# Shield00.net
KiCad netlist of a schematic drawn in EAGLE
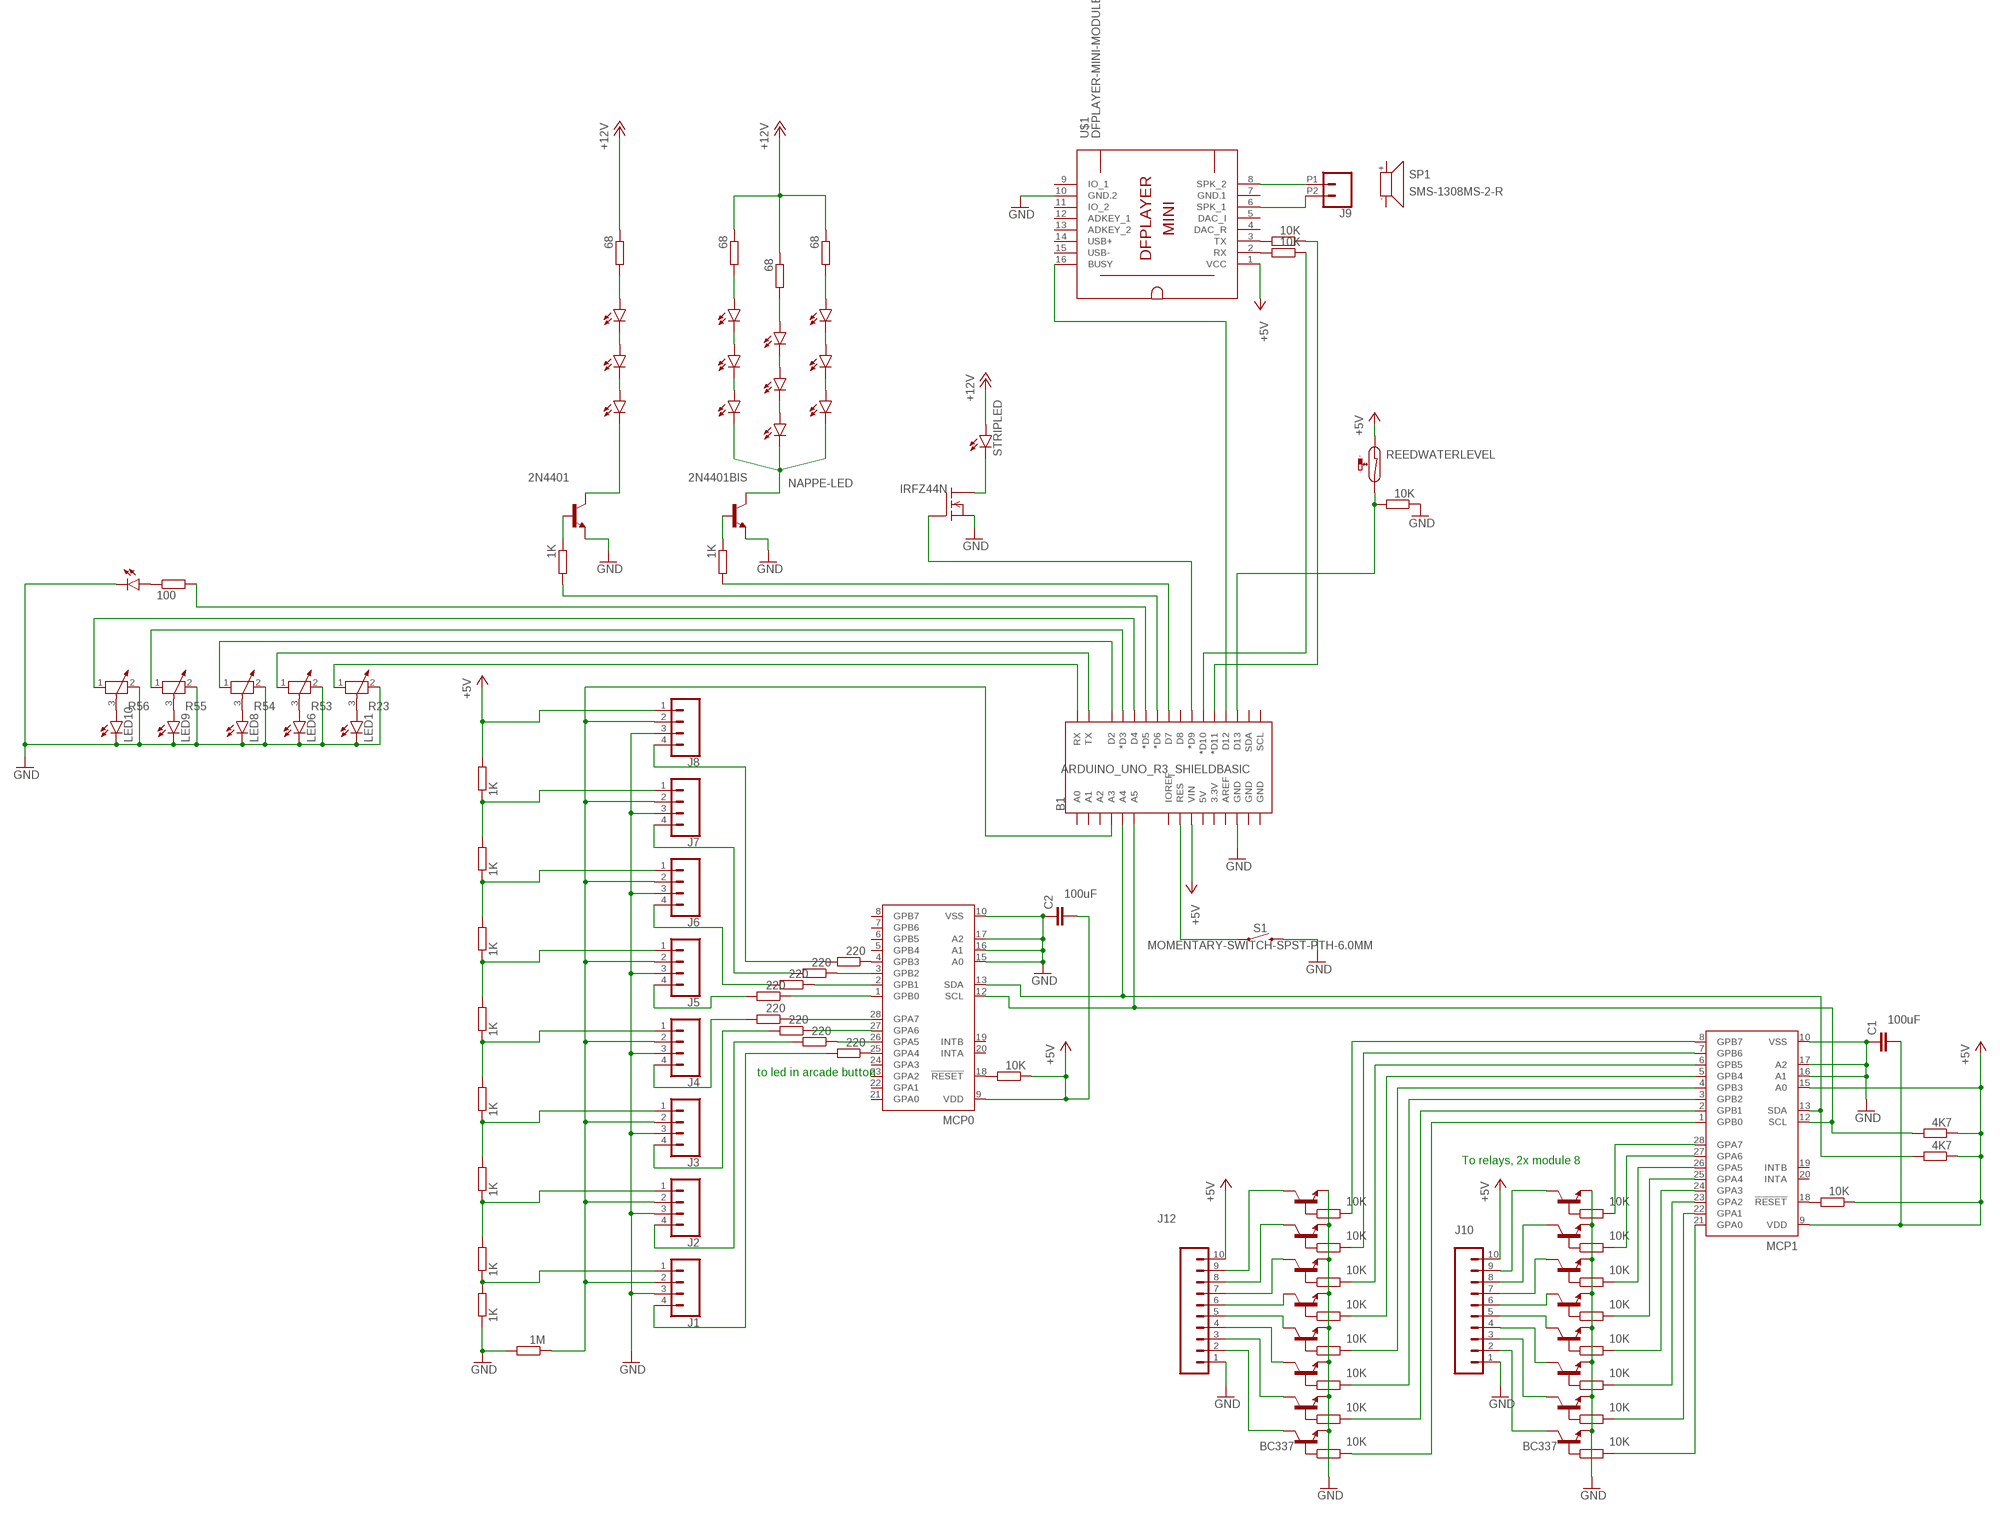
[diagram p0: schematic, sheet 1]

(export (version "E")
  (design (tool "Eeschema 10.0.6"))
  (components
    (comp (ref "2N4401")
      (value "2N4416")
      (footprint "eagle-import:TO92")
      (libsource (lib "eagle-import") (part "2N4416"))
    )
    (comp (ref "2N4401BIS")
      (value "2N4416")
      (footprint "eagle-import:TO92")
      (libsource (lib "eagle-import") (part "2N4416"))
    )
    (comp (ref "B1")
      (value "ARDUINO_UNO_R3_SHIELDBASIC")
      (footprint "eagle-import:UNO_R3_SHIELD")
      (libsource (lib "eagle-import") (part "ARDUINO_UNO_R3_SHIELDBASIC"))
    )
    (comp (ref "C1")
      (value "100uF")
      (footprint "eagle-import:C5B3")
      (libsource (lib "eagle-import") (part "C5/3"))
    )
    (comp (ref "C2")
      (value "100uF")
      (footprint "eagle-import:C5B3")
      (libsource (lib "eagle-import") (part "C5/3"))
    )
    (comp (ref "IRFZ44N")
      (value "IRF840")
      (footprint "eagle-import:TO220")
      (libsource (lib "eagle-import") (part "IRF840"))
    )
    (comp (ref "J1")
      (value "CONN_04JST-PTH-VERT")
      (footprint "eagle-import:JST-4-PTH-VERT")
      (libsource (lib "eagle-import") (part "CONN_04JST-PTH-VERT"))
    )
    (comp (ref "J2")
      (value "CONN_04JST-PTH-VERT")
      (footprint "eagle-import:JST-4-PTH-VERT")
      (libsource (lib "eagle-import") (part "CONN_04JST-PTH-VERT"))
    )
    (comp (ref "J3")
      (value "CONN_04JST-PTH-VERT")
      (footprint "eagle-import:JST-4-PTH-VERT")
      (libsource (lib "eagle-import") (part "CONN_04JST-PTH-VERT"))
    )
    (comp (ref "J4")
      (value "CONN_04JST-PTH-VERT")
      (footprint "eagle-import:JST-4-PTH-VERT")
      (libsource (lib "eagle-import") (part "CONN_04JST-PTH-VERT"))
    )
    (comp (ref "J5")
      (value "CONN_04JST-PTH-VERT")
      (footprint "eagle-import:JST-4-PTH-VERT")
      (libsource (lib "eagle-import") (part "CONN_04JST-PTH-VERT"))
    )
    (comp (ref "J6")
      (value "CONN_04JST-PTH-VERT")
      (footprint "eagle-import:JST-4-PTH-VERT")
      (libsource (lib "eagle-import") (part "CONN_04JST-PTH-VERT"))
    )
    (comp (ref "J7")
      (value "CONN_04JST-PTH-VERT")
      (footprint "eagle-import:JST-4-PTH-VERT")
      (libsource (lib "eagle-import") (part "CONN_04JST-PTH-VERT"))
    )
    (comp (ref "J8")
      (value "CONN_04JST-PTH-VERT")
      (footprint "eagle-import:JST-4-PTH-VERT")
      (libsource (lib "eagle-import") (part "CONN_04JST-PTH-VERT"))
    )
    (comp (ref "J9")
      (value "CONN_022.54MM_SCREWTERM")
      (footprint "eagle-import:1X02_2.54_SCREWTERM")
      (libsource (lib "eagle-import") (part "CONN_022.54MM_SCREWTERM"))
    )
    (comp (ref "J10")
      (value "CONN_10\"")
      (footprint "eagle-import:1X10")
      (libsource (lib "eagle-import") (part "CONN_10{dblquote}"))
    )
    (comp (ref "J12")
      (value "CONN_10\"")
      (footprint "eagle-import:1X10")
      (libsource (lib "eagle-import") (part "CONN_10{dblquote}"))
    )
    (comp (ref "LED1")
      (value "LED5MM")
      (footprint "eagle-import:LED5MM")
      (libsource (lib "eagle-import") (part "LED5MM"))
    )
    (comp (ref "LED6")
      (value "LED5MM")
      (footprint "eagle-import:LED5MM")
      (libsource (lib "eagle-import") (part "LED5MM"))
    )
    (comp (ref "LED8")
      (value "LED5MM")
      (footprint "eagle-import:LED5MM")
      (libsource (lib "eagle-import") (part "LED5MM"))
    )
    (comp (ref "LED9")
      (value "LED5MM")
      (footprint "eagle-import:LED5MM")
      (libsource (lib "eagle-import") (part "LED5MM"))
    )
    (comp (ref "LED10")
      (value "LED5MM")
      (footprint "eagle-import:LED5MM")
      (libsource (lib "eagle-import") (part "LED5MM"))
    )
    (comp (ref "MCP0")
      (value "MCP23017SO")
      (footprint "eagle-import:SO28W")
      (fields (field (name "MF") "MICROCHIP") (field (name "MPN") "MCP23017-E/SO"))
      (libsource (lib "eagle-import") (part "MCP23017SO"))
    )
    (comp (ref "MCP1")
      (value "MCP23017SO")
      (footprint "eagle-import:SO28W")
      (fields (field (name "MF") "MICROCHIP") (field (name "MPN") "MCP23017-E/SO"))
      (libsource (lib "eagle-import") (part "MCP23017SO"))
    )
    (comp (ref "NAPPE-LED")
      (value "LED5MM")
      (footprint "eagle-import:LED5MM")
      (libsource (lib "eagle-import") (part "LED5MM"))
    )
    (comp (ref "NAPPE-LED1")
      (value "LED5MM")
      (footprint "eagle-import:LED5MM")
      (libsource (lib "eagle-import") (part "LED5MM"))
    )
    (comp (ref "NAPPE-LED2")
      (value "LED5MM")
      (footprint "eagle-import:LED5MM")
      (libsource (lib "eagle-import") (part "LED5MM"))
    )
    (comp (ref "NAPPE-LED3")
      (value "LED5MM")
      (footprint "eagle-import:LED5MM")
      (libsource (lib "eagle-import") (part "LED5MM"))
    )
    (comp (ref "NAPPE-LED4")
      (value "LED5MM")
      (footprint "eagle-import:LED5MM")
      (libsource (lib "eagle-import") (part "LED5MM"))
    )
    (comp (ref "NAPPE-LED5")
      (value "LED5MM")
      (footprint "eagle-import:LED5MM")
      (libsource (lib "eagle-import") (part "LED5MM"))
    )
    (comp (ref "NAPPE-LED6")
      (value "LED5MM")
      (footprint "eagle-import:LED5MM")
      (libsource (lib "eagle-import") (part "LED5MM"))
    )
    (comp (ref "NAPPE-LED7")
      (value "LED5MM")
      (footprint "eagle-import:LED5MM")
      (libsource (lib "eagle-import") (part "LED5MM"))
    )
    (comp (ref "NAPPE-LED8")
      (value "LED5MM")
      (footprint "eagle-import:LED5MM")
      (libsource (lib "eagle-import") (part "LED5MM"))
    )
    (comp (ref "NAPPE-LED9")
      (value "LED5MM")
      (footprint "eagle-import:LED5MM")
      (libsource (lib "eagle-import") (part "LED5MM"))
    )
    (comp (ref "NAPPE-LED10")
      (value "LED5MM")
      (footprint "eagle-import:LED5MM")
      (libsource (lib "eagle-import") (part "LED5MM"))
    )
    (comp (ref "NAPPE-LED11")
      (value "LED5MM")
      (footprint "eagle-import:LED5MM")
      (libsource (lib "eagle-import") (part "LED5MM"))
    )
    (comp (ref "NAPPE-LED12")
      (value "LED5MM")
      (footprint "eagle-import:LED5MM")
      (libsource (lib "eagle-import") (part "LED5MM"))
    )
    (comp (ref "R1")
      (value "1K")
      (footprint "eagle-import:R0805")
      (libsource (lib "eagle-import") (part "R-EU_R0805"))
    )
    (comp (ref "R2")
      (value "1M")
      (footprint "eagle-import:R0805")
      (libsource (lib "eagle-import") (part "R-EU_R0805"))
    )
    (comp (ref "R3")
      (value "1K")
      (footprint "eagle-import:R0805")
      (libsource (lib "eagle-import") (part "R-EU_R0805"))
    )
    (comp (ref "R4")
      (value "1K")
      (footprint "eagle-import:R0805")
      (libsource (lib "eagle-import") (part "R-EU_R0805"))
    )
    (comp (ref "R5")
      (value "1K")
      (footprint "eagle-import:R0805")
      (libsource (lib "eagle-import") (part "R-EU_R0805"))
    )
    (comp (ref "R6")
      (value "1K")
      (footprint "eagle-import:R0805")
      (libsource (lib "eagle-import") (part "R-EU_R0805"))
    )
    (comp (ref "R7")
      (value "1K")
      (footprint "eagle-import:R0805")
      (libsource (lib "eagle-import") (part "R-EU_R0805"))
    )
    (comp (ref "R8")
      (value "1K")
      (footprint "eagle-import:R0805")
      (libsource (lib "eagle-import") (part "R-EU_R0805"))
    )
    (comp (ref "R9")
      (value "1K")
      (footprint "eagle-import:R0805")
      (libsource (lib "eagle-import") (part "R-EU_R0805"))
    )
    (comp (ref "R10")
      (value "10K")
      (footprint "eagle-import:R0805")
      (libsource (lib "eagle-import") (part "R-EU_R0805"))
    )
    (comp (ref "R11")
      (value "220")
      (footprint "eagle-import:R0805")
      (libsource (lib "eagle-import") (part "R-EU_R0805"))
    )
    (comp (ref "R12")
      (value "220")
      (footprint "eagle-import:R0805")
      (libsource (lib "eagle-import") (part "R-EU_R0805"))
    )
    (comp (ref "R13")
      (value "220")
      (footprint "eagle-import:R0805")
      (libsource (lib "eagle-import") (part "R-EU_R0805"))
    )
    (comp (ref "R14")
      (value "220")
      (footprint "eagle-import:R0805")
      (libsource (lib "eagle-import") (part "R-EU_R0805"))
    )
    (comp (ref "R15")
      (value "220")
      (footprint "eagle-import:R0805")
      (libsource (lib "eagle-import") (part "R-EU_R0805"))
    )
    (comp (ref "R16")
      (value "220")
      (footprint "eagle-import:R0805")
      (libsource (lib "eagle-import") (part "R-EU_R0805"))
    )
    (comp (ref "R17")
      (value "220")
      (footprint "eagle-import:R0805")
      (libsource (lib "eagle-import") (part "R-EU_R0805"))
    )
    (comp (ref "R18")
      (value "220")
      (footprint "eagle-import:R0805")
      (libsource (lib "eagle-import") (part "R-EU_R0805"))
    )
    (comp (ref "R19")
      (value "10K")
      (footprint "eagle-import:R0805")
      (libsource (lib "eagle-import") (part "R-EU_R0805"))
    )
    (comp (ref "R20")
      (value "10K")
      (footprint "eagle-import:R0805")
      (libsource (lib "eagle-import") (part "R-EU_R0805"))
    )
    (comp (ref "R21")
      (value "10K")
      (footprint "eagle-import:R0805")
      (libsource (lib "eagle-import") (part "R-EU_R0805"))
    )
    (comp (ref "R22")
      (value "10K")
      (footprint "eagle-import:R0805")
      (libsource (lib "eagle-import") (part "R-EU_R0805"))
    )
    (comp (ref "R23")
      (value "POTENTIOMETER_PT-10")
      (footprint "eagle-import:PT-10")
      (libsource (lib "eagle-import") (part "POTENTIOMETER_PT-10"))
    )
    (comp (ref "R24")
      (value "4K7")
      (footprint "eagle-import:R0805")
      (libsource (lib "eagle-import") (part "R-EU_R0805"))
    )
    (comp (ref "R25")
      (value "4K7")
      (footprint "eagle-import:R0805")
      (libsource (lib "eagle-import") (part "R-EU_R0805"))
    )
    (comp (ref "R26")
      (value "1K")
      (footprint "eagle-import:R0805")
      (libsource (lib "eagle-import") (part "R-EU_R0805"))
    )
    (comp (ref "R27")
      (value "10K")
      (footprint "eagle-import:R0805")
      (libsource (lib "eagle-import") (part "R-EU_R0805"))
    )
    (comp (ref "R28")
      (value "10K")
      (footprint "eagle-import:R0805")
      (libsource (lib "eagle-import") (part "R-EU_R0805"))
    )
    (comp (ref "R29")
      (value "10K")
      (footprint "eagle-import:R0805")
      (libsource (lib "eagle-import") (part "R-EU_R0805"))
    )
    (comp (ref "R30")
      (value "10K")
      (footprint "eagle-import:R0805")
      (libsource (lib "eagle-import") (part "R-EU_R0805"))
    )
    (comp (ref "R31")
      (value "10K")
      (footprint "eagle-import:R0805")
      (libsource (lib "eagle-import") (part "R-EU_R0805"))
    )
    (comp (ref "R32")
      (value "10K")
      (footprint "eagle-import:R0805")
      (libsource (lib "eagle-import") (part "R-EU_R0805"))
    )
    (comp (ref "R33")
      (value "10K")
      (footprint "eagle-import:R0805")
      (libsource (lib "eagle-import") (part "R-EU_R0805"))
    )
    (comp (ref "R34")
      (value "10K")
      (footprint "eagle-import:R0805")
      (libsource (lib "eagle-import") (part "R-EU_R0805"))
    )
    (comp (ref "R35")
      (value "10K")
      (footprint "eagle-import:R0805")
      (libsource (lib "eagle-import") (part "R-EU_R0805"))
    )
    (comp (ref "R36")
      (value "10K")
      (footprint "eagle-import:R0805")
      (libsource (lib "eagle-import") (part "R-EU_R0805"))
    )
    (comp (ref "R37")
      (value "10K")
      (footprint "eagle-import:R0805")
      (libsource (lib "eagle-import") (part "R-EU_R0805"))
    )
    (comp (ref "R38")
      (value "10K")
      (footprint "eagle-import:R0805")
      (libsource (lib "eagle-import") (part "R-EU_R0805"))
    )
    (comp (ref "R39")
      (value "10K")
      (footprint "eagle-import:R0805")
      (libsource (lib "eagle-import") (part "R-EU_R0805"))
    )
    (comp (ref "R40")
      (value "10K")
      (footprint "eagle-import:R0805")
      (libsource (lib "eagle-import") (part "R-EU_R0805"))
    )
    (comp (ref "R41")
      (value "10K")
      (footprint "eagle-import:R0805")
      (libsource (lib "eagle-import") (part "R-EU_R0805"))
    )
    (comp (ref "R42")
      (value "10K")
      (footprint "eagle-import:R0805")
      (libsource (lib "eagle-import") (part "R-EU_R0805"))
    )
    (comp (ref "R43")
      (value "1K")
      (footprint "eagle-import:R0805")
      (libsource (lib "eagle-import") (part "R-EU_R0805"))
    )
    (comp (ref "R47")
      (value "68")
      (footprint "eagle-import:R0805")
      (libsource (lib "eagle-import") (part "R-EU_R0805"))
    )
    (comp (ref "R49")
      (value "68")
      (footprint "eagle-import:R0805")
      (libsource (lib "eagle-import") (part "R-EU_R0805"))
    )
    (comp (ref "R50")
      (value "68")
      (footprint "eagle-import:R0805")
      (libsource (lib "eagle-import") (part "R-EU_R0805"))
    )
    (comp (ref "R51")
      (value "68")
      (footprint "eagle-import:R0805")
      (libsource (lib "eagle-import") (part "R-EU_R0805"))
    )
    (comp (ref "R52")
      (value "100")
      (footprint "eagle-import:R0805")
      (libsource (lib "eagle-import") (part "R-EU_R0805"))
    )
    (comp (ref "R53")
      (value "POTENTIOMETER_PT-10")
      (footprint "eagle-import:PT-10")
      (libsource (lib "eagle-import") (part "POTENTIOMETER_PT-10"))
    )
    (comp (ref "R54")
      (value "POTENTIOMETER_PT-10")
      (footprint "eagle-import:PT-10")
      (libsource (lib "eagle-import") (part "POTENTIOMETER_PT-10"))
    )
    (comp (ref "R55")
      (value "POTENTIOMETER_PT-10")
      (footprint "eagle-import:PT-10")
      (libsource (lib "eagle-import") (part "POTENTIOMETER_PT-10"))
    )
    (comp (ref "R56")
      (value "POTENTIOMETER_PT-10")
      (footprint "eagle-import:PT-10")
      (libsource (lib "eagle-import") (part "POTENTIOMETER_PT-10"))
    )
    (comp (ref "REEDWATERLEVEL")
      (value "REED-SWITCH-MK6-5-B")
      (footprint "eagle-import:MK6-5")
      (fields (field (name "MF") "MEDER") (field (name "MPN") "MK6-5-B"))
      (libsource (lib "eagle-import") (part "REED-SWITCH-MK6-5-B"))
    )
    (comp (ref "S1")
      (value "MOMENTARY-SWITCH-SPST-PTH-6.0MM")
      (footprint "eagle-import:TACTILE_SWITCH_PTH_6.0MM")
      (libsource (lib "eagle-import") (part "MOMENTARY-SWITCH-SPST-PTH-6.0MM"))
    )
    (comp (ref "SP1")
      (value "SMS-1308MS-2-R")
      (footprint "eagle-import:SMS-1308MS-2-R")
      (libsource (lib "eagle-import") (part "SMS-1308MS-2-R"))
    )
    (comp (ref "STRIPLED")
      (value "LED5MM")
      (footprint "eagle-import:LED5MM")
      (libsource (lib "eagle-import") (part "LED5MM"))
    )
    (comp (ref "T1")
      (value "BC337")
      (footprint "eagle-import:TO92")
      (libsource (lib "eagle-import") (part "BC337"))
    )
    (comp (ref "T2")
      (value "BC337")
      (footprint "eagle-import:TO92")
      (libsource (lib "eagle-import") (part "BC337"))
    )
    (comp (ref "T3")
      (value "BC337")
      (footprint "eagle-import:TO92")
      (libsource (lib "eagle-import") (part "BC337"))
    )
    (comp (ref "T4")
      (value "BC337")
      (footprint "eagle-import:TO92")
      (libsource (lib "eagle-import") (part "BC337"))
    )
    (comp (ref "T5")
      (value "BC337")
      (footprint "eagle-import:TO92")
      (libsource (lib "eagle-import") (part "BC337"))
    )
    (comp (ref "T6")
      (value "BC337")
      (footprint "eagle-import:TO92")
      (libsource (lib "eagle-import") (part "BC337"))
    )
    (comp (ref "T7")
      (value "BC337")
      (footprint "eagle-import:TO92")
      (libsource (lib "eagle-import") (part "BC337"))
    )
    (comp (ref "T8")
      (value "BC337")
      (footprint "eagle-import:TO92")
      (libsource (lib "eagle-import") (part "BC337"))
    )
    (comp (ref "T9")
      (value "BC337")
      (footprint "eagle-import:TO92")
      (libsource (lib "eagle-import") (part "BC337"))
    )
    (comp (ref "T10")
      (value "BC337")
      (footprint "eagle-import:TO92")
      (libsource (lib "eagle-import") (part "BC337"))
    )
    (comp (ref "T11")
      (value "BC337")
      (footprint "eagle-import:TO92")
      (libsource (lib "eagle-import") (part "BC337"))
    )
    (comp (ref "T12")
      (value "BC337")
      (footprint "eagle-import:TO92")
      (libsource (lib "eagle-import") (part "BC337"))
    )
    (comp (ref "T13")
      (value "BC337")
      (footprint "eagle-import:TO92")
      (libsource (lib "eagle-import") (part "BC337"))
    )
    (comp (ref "T14")
      (value "BC337")
      (footprint "eagle-import:TO92")
      (libsource (lib "eagle-import") (part "BC337"))
    )
    (comp (ref "T15")
      (value "BC337")
      (footprint "eagle-import:TO92")
      (libsource (lib "eagle-import") (part "BC337"))
    )
    (comp (ref "T16")
      (value "BC337")
      (footprint "eagle-import:TO92")
      (libsource (lib "eagle-import") (part "BC337"))
    )
    (comp (ref "U$1")
      (value "DFPLAYER-MINI-MODULE")
      (footprint "eagle-import:DFPLAYER-MINI-MODULE")
      (libsource (lib "eagle-import") (part "DFPLAYER-MINI-MODULE"))
    )
  )
  (nets
    (net (code "1") (name "+5V") (class "Default")
      (node (ref "B1") (pin "VIN") (pinfunction "VIN_VIN") (pintype "bidirectional"))
      (node (ref "C1") (pin "2") (pinfunction "2_2") (pintype "passive"))
      (node (ref "C2") (pin "2") (pinfunction "2_2") (pintype "passive"))
      (node (ref "J10") (pin "10") (pinfunction "10_10") (pintype "passive"))
      (node (ref "J12") (pin "10") (pinfunction "10_10") (pintype "passive"))
      (node (ref "J8") (pin "1") (pinfunction "1_1") (pintype "passive"))
      (node (ref "MCP0") (pin "9") (pinfunction "VDD_9") (pintype "power_in"))
      (node (ref "MCP1") (pin "15") (pinfunction "A0_15") (pintype "input"))
      (node (ref "MCP1") (pin "9") (pinfunction "VDD_9") (pintype "power_in"))
      (node (ref "R20") (pin "1") (pinfunction "1_1") (pintype "passive"))
      (node (ref "R22") (pin "1") (pinfunction "1_1") (pintype "passive"))
      (node (ref "R24") (pin "1") (pinfunction "1_1") (pintype "passive"))
      (node (ref "R25") (pin "1") (pinfunction "1_1") (pintype "passive"))
      (node (ref "R9") (pin "2") (pinfunction "2_2") (pintype "passive"))
      (node (ref "REEDWATERLEVEL") (pin "1") (pinfunction "1_1") (pintype "passive"))
      (node (ref "U$1") (pin "1") (pinfunction "VCC_1") (pintype "power_in"))
    )
    (net (code "2") (name "+12V") (class "Default")
      (node (ref "R47") (pin "1") (pinfunction "1_1") (pintype "passive"))
      (node (ref "R49") (pin "1") (pinfunction "1_1") (pintype "passive"))
      (node (ref "R50") (pin "1") (pinfunction "1_1") (pintype "passive"))
      (node (ref "R51") (pin "1") (pinfunction "1_1") (pintype "passive"))
      (node (ref "STRIPLED") (pin "A") (pinfunction "A_A") (pintype "passive"))
    )
    (net (code "3") (name "/GND.1") (class "Default")
      (node (ref "U$1") (pin "7") (pinfunction "GND.1_7") (pintype "power_in"))
    )
    (net (code "4") (name "GND") (class "Default")
      (node (ref "2N4401") (pin "3") (pinfunction "E_3") (pintype "passive"))
      (node (ref "2N4401BIS") (pin "3") (pinfunction "E_3") (pintype "passive"))
      (node (ref "B1") (pin "GND@2") (pinfunction "GND_GND@2") (pintype "bidirectional"))
      (node (ref "C1") (pin "1") (pinfunction "1_1") (pintype "passive"))
      (node (ref "C2") (pin "1") (pinfunction "1_1") (pintype "passive"))
      (node (ref "IRFZ44N") (pin "3") (pinfunction "S_3") (pintype "passive"))
      (node (ref "J1") (pin "3") (pinfunction "3_3") (pintype "passive"))
      (node (ref "J10") (pin "1") (pinfunction "1_1") (pintype "passive"))
      (node (ref "J12") (pin "1") (pinfunction "1_1") (pintype "passive"))
      (node (ref "J2") (pin "3") (pinfunction "3_3") (pintype "passive"))
      (node (ref "J3") (pin "3") (pinfunction "3_3") (pintype "passive"))
      (node (ref "J4") (pin "3") (pinfunction "3_3") (pintype "passive"))
      (node (ref "J5") (pin "3") (pinfunction "3_3") (pintype "passive"))
      (node (ref "J6") (pin "3") (pinfunction "3_3") (pintype "passive"))
      (node (ref "J7") (pin "3") (pinfunction "3_3") (pintype "passive"))
      (node (ref "J8") (pin "3") (pinfunction "3_3") (pintype "passive"))
      (node (ref "LED1") (pin "K") (pinfunction "C_K") (pintype "passive"))
      (node (ref "LED10") (pin "K") (pinfunction "C_K") (pintype "passive"))
      (node (ref "LED6") (pin "K") (pinfunction "C_K") (pintype "passive"))
      (node (ref "LED8") (pin "K") (pinfunction "C_K") (pintype "passive"))
      (node (ref "LED9") (pin "K") (pinfunction "C_K") (pintype "passive"))
      (node (ref "MCP0") (pin "10") (pinfunction "VSS_10") (pintype "power_in"))
      (node (ref "MCP0") (pin "15") (pinfunction "A0_15") (pintype "input"))
      (node (ref "MCP0") (pin "16") (pinfunction "A1_16") (pintype "input"))
      (node (ref "MCP0") (pin "17") (pinfunction "A2_17") (pintype "input"))
      (node (ref "MCP1") (pin "10") (pinfunction "VSS_10") (pintype "power_in"))
      (node (ref "MCP1") (pin "16") (pinfunction "A1_16") (pintype "input"))
      (node (ref "MCP1") (pin "17") (pinfunction "A2_17") (pintype "input"))
      (node (ref "NAPPE-LED12") (pin "K") (pinfunction "C_K") (pintype "passive"))
      (node (ref "R1") (pin "1") (pinfunction "1_1") (pintype "passive"))
      (node (ref "R2") (pin "2") (pinfunction "2_2") (pintype "passive"))
      (node (ref "R21") (pin "1") (pinfunction "1_1") (pintype "passive"))
      (node (ref "R23") (pin "2") (pinfunction "2_2") (pintype "passive"))
      (node (ref "R53") (pin "2") (pinfunction "2_2") (pintype "passive"))
      (node (ref "R54") (pin "2") (pinfunction "2_2") (pintype "passive"))
      (node (ref "R55") (pin "2") (pinfunction "2_2") (pintype "passive"))
      (node (ref "R56") (pin "2") (pinfunction "2_2") (pintype "passive"))
      (node (ref "S1") (pin "3") (pinfunction "2_3") (pintype "passive"))
      (node (ref "T1") (pin "1") (pinfunction "E_1") (pintype "passive"))
      (node (ref "T10") (pin "1") (pinfunction "E_1") (pintype "passive"))
      (node (ref "T11") (pin "1") (pinfunction "E_1") (pintype "passive"))
      (node (ref "T12") (pin "1") (pinfunction "E_1") (pintype "passive"))
      (node (ref "T13") (pin "1") (pinfunction "E_1") (pintype "passive"))
      (node (ref "T14") (pin "1") (pinfunction "E_1") (pintype "passive"))
      (node (ref "T15") (pin "1") (pinfunction "E_1") (pintype "passive"))
      (node (ref "T16") (pin "1") (pinfunction "E_1") (pintype "passive"))
      (node (ref "T2") (pin "1") (pinfunction "E_1") (pintype "passive"))
      (node (ref "T3") (pin "1") (pinfunction "E_1") (pintype "passive"))
      (node (ref "T4") (pin "1") (pinfunction "E_1") (pintype "passive"))
      (node (ref "T5") (pin "1") (pinfunction "E_1") (pintype "passive"))
      (node (ref "T6") (pin "1") (pinfunction "E_1") (pintype "passive"))
      (node (ref "T7") (pin "1") (pinfunction "E_1") (pintype "passive"))
      (node (ref "T8") (pin "1") (pinfunction "E_1") (pintype "passive"))
      (node (ref "T9") (pin "1") (pinfunction "E_1") (pintype "passive"))
      (node (ref "U$1") (pin "10") (pinfunction "GND.2_10") (pintype "power_in"))
    )
    (net (code "5") (name "Net-(2N4401-B)") (class "Default")
      (node (ref "2N4401") (pin "2") (pinfunction "B_2") (pintype "passive"))
      (node (ref "R26") (pin "1") (pinfunction "1_1") (pintype "passive"))
    )
    (net (code "6") (name "Net-(2N4401-C)") (class "Default")
      (node (ref "2N4401") (pin "1") (pinfunction "C_1") (pintype "passive"))
      (node (ref "NAPPE-LED9") (pin "K") (pinfunction "C_K") (pintype "passive"))
    )
    (net (code "7") (name "Net-(2N4401BIS-B)") (class "Default")
      (node (ref "2N4401BIS") (pin "2") (pinfunction "B_2") (pintype "passive"))
      (node (ref "R43") (pin "1") (pinfunction "1_1") (pintype "passive"))
    )
    (net (code "8") (name "Net-(2N4401BIS-C)") (class "Default")
      (node (ref "2N4401BIS") (pin "1") (pinfunction "C_1") (pintype "passive"))
      (node (ref "NAPPE-LED") (pin "K") (pinfunction "C_K") (pintype "passive"))
      (node (ref "NAPPE-LED3") (pin "K") (pinfunction "C_K") (pintype "passive"))
      (node (ref "NAPPE-LED6") (pin "K") (pinfunction "C_K") (pintype "passive"))
    )
    (net (code "9") (name "Net-(B1-*D3)") (class "Default")
      (node (ref "B1") (pin "D3") (pinfunction "*D3_D3") (pintype "bidirectional"))
      (node (ref "R55") (pin "1") (pinfunction "1_1") (pintype "passive"))
    )
    (net (code "10") (name "Net-(B1-*D5)") (class "Default")
      (node (ref "B1") (pin "D5") (pinfunction "*D5_D5") (pintype "bidirectional"))
      (node (ref "R52") (pin "2") (pinfunction "2_2") (pintype "passive"))
    )
    (net (code "11") (name "Net-(B1-*D6)") (class "Default")
      (node (ref "B1") (pin "D6") (pinfunction "*D6_D6") (pintype "bidirectional"))
      (node (ref "R26") (pin "2") (pinfunction "2_2") (pintype "passive"))
    )
    (net (code "12") (name "Net-(B1-*D9)") (class "Default")
      (node (ref "B1") (pin "D9") (pinfunction "*D9_D9") (pintype "bidirectional"))
      (node (ref "IRFZ44N") (pin "1") (pinfunction "G_1") (pintype "passive"))
    )
    (net (code "13") (name "Net-(B1-*D10)") (class "Default")
      (node (ref "B1") (pin "D10") (pinfunction "*D10_D10") (pintype "bidirectional"))
      (node (ref "R19") (pin "1") (pinfunction "1_1") (pintype "passive"))
    )
    (net (code "14") (name "Net-(B1-*D11)") (class "Default")
      (node (ref "B1") (pin "D11") (pinfunction "*D11_D11") (pintype "bidirectional"))
      (node (ref "R10") (pin "1") (pinfunction "1_1") (pintype "passive"))
    )
    (net (code "15") (name "Net-(B1-PadA3)") (class "Default")
      (node (ref "B1") (pin "A3") (pinfunction "A3_A3") (pintype "bidirectional"))
      (node (ref "J1") (pin "2") (pinfunction "2_2") (pintype "passive"))
      (node (ref "J2") (pin "2") (pinfunction "2_2") (pintype "passive"))
      (node (ref "J3") (pin "2") (pinfunction "2_2") (pintype "passive"))
      (node (ref "J4") (pin "2") (pinfunction "2_2") (pintype "passive"))
      (node (ref "J5") (pin "2") (pinfunction "2_2") (pintype "passive"))
      (node (ref "J6") (pin "2") (pinfunction "2_2") (pintype "passive"))
      (node (ref "J7") (pin "2") (pinfunction "2_2") (pintype "passive"))
      (node (ref "J8") (pin "2") (pinfunction "2_2") (pintype "passive"))
      (node (ref "R2") (pin "1") (pinfunction "1_1") (pintype "passive"))
    )
    (net (code "16") (name "Net-(B1-PadD2)") (class "Default")
      (node (ref "B1") (pin "D2") (pinfunction "D2_D2") (pintype "bidirectional"))
      (node (ref "R54") (pin "1") (pinfunction "1_1") (pintype "passive"))
    )
    (net (code "17") (name "Net-(B1-PadD4)") (class "Default")
      (node (ref "B1") (pin "D4") (pinfunction "D4_D4") (pintype "bidirectional"))
      (node (ref "R56") (pin "1") (pinfunction "1_1") (pintype "passive"))
    )
    (net (code "18") (name "Net-(B1-PadD7)") (class "Default")
      (node (ref "B1") (pin "D7") (pinfunction "D7_D7") (pintype "bidirectional"))
      (node (ref "R43") (pin "2") (pinfunction "2_2") (pintype "passive"))
    )
    (net (code "19") (name "Net-(B1-PadD13)") (class "Default")
      (node (ref "B1") (pin "D13") (pinfunction "D13_D13") (pintype "bidirectional"))
      (node (ref "R21") (pin "2") (pinfunction "2_2") (pintype "passive"))
      (node (ref "REEDWATERLEVEL") (pin "2") (pinfunction "2_2") (pintype "passive"))
    )
    (net (code "20") (name "Net-(B1-PadRES)") (class "Default")
      (node (ref "B1") (pin "RES") (pinfunction "RES_RES") (pintype "bidirectional"))
      (node (ref "S1") (pin "1") (pinfunction "1_1") (pintype "passive"))
    )
    (net (code "21") (name "Net-(B1-PadRX)") (class "Default")
      (node (ref "B1") (pin "RX") (pinfunction "RX_RX") (pintype "bidirectional"))
      (node (ref "R23") (pin "1") (pinfunction "1_1") (pintype "passive"))
    )
    (net (code "22") (name "Net-(B1-PadTX)") (class "Default")
      (node (ref "B1") (pin "TX") (pinfunction "TX_TX") (pintype "bidirectional"))
      (node (ref "R53") (pin "1") (pinfunction "1_1") (pintype "passive"))
    )
    (net (code "23") (name "Net-(IRFZ44N-D)") (class "Default")
      (node (ref "IRFZ44N") (pin "2") (pinfunction "D_2") (pintype "passive"))
      (node (ref "STRIPLED") (pin "K") (pinfunction "C_K") (pintype "passive"))
    )
    (net (code "24") (name "Net-(J1-Pad1)") (class "Default")
      (node (ref "J1") (pin "1") (pinfunction "1_1") (pintype "passive"))
      (node (ref "R1") (pin "2") (pinfunction "2_2") (pintype "passive"))
      (node (ref "R3") (pin "1") (pinfunction "1_1") (pintype "passive"))
    )
    (net (code "25") (name "Net-(J1-Pad4)") (class "Default")
      (node (ref "J1") (pin "4") (pinfunction "4_4") (pintype "passive"))
      (node (ref "R11") (pin "2") (pinfunction "2_2") (pintype "passive"))
    )
    (net (code "26") (name "Net-(J2-Pad1)") (class "Default")
      (node (ref "J2") (pin "1") (pinfunction "1_1") (pintype "passive"))
      (node (ref "R3") (pin "2") (pinfunction "2_2") (pintype "passive"))
      (node (ref "R4") (pin "1") (pinfunction "1_1") (pintype "passive"))
    )
    (net (code "27") (name "Net-(J2-Pad4)") (class "Default")
      (node (ref "J2") (pin "4") (pinfunction "4_4") (pintype "passive"))
      (node (ref "R12") (pin "2") (pinfunction "2_2") (pintype "passive"))
    )
    (net (code "28") (name "Net-(J3-Pad1)") (class "Default")
      (node (ref "J3") (pin "1") (pinfunction "1_1") (pintype "passive"))
      (node (ref "R4") (pin "2") (pinfunction "2_2") (pintype "passive"))
      (node (ref "R5") (pin "1") (pinfunction "1_1") (pintype "passive"))
    )
    (net (code "29") (name "Net-(J3-Pad4)") (class "Default")
      (node (ref "J3") (pin "4") (pinfunction "4_4") (pintype "passive"))
      (node (ref "R13") (pin "2") (pinfunction "2_2") (pintype "passive"))
    )
    (net (code "30") (name "Net-(J4-Pad1)") (class "Default")
      (node (ref "J4") (pin "1") (pinfunction "1_1") (pintype "passive"))
      (node (ref "R5") (pin "2") (pinfunction "2_2") (pintype "passive"))
      (node (ref "R6") (pin "1") (pinfunction "1_1") (pintype "passive"))
    )
    (net (code "31") (name "Net-(J4-Pad4)") (class "Default")
      (node (ref "J4") (pin "4") (pinfunction "4_4") (pintype "passive"))
      (node (ref "R14") (pin "2") (pinfunction "2_2") (pintype "passive"))
    )
    (net (code "32") (name "Net-(J5-Pad1)") (class "Default")
      (node (ref "J5") (pin "1") (pinfunction "1_1") (pintype "passive"))
      (node (ref "R6") (pin "2") (pinfunction "2_2") (pintype "passive"))
      (node (ref "R7") (pin "1") (pinfunction "1_1") (pintype "passive"))
    )
    (net (code "33") (name "Net-(J5-Pad4)") (class "Default")
      (node (ref "J5") (pin "4") (pinfunction "4_4") (pintype "passive"))
      (node (ref "R15") (pin "2") (pinfunction "2_2") (pintype "passive"))
    )
    (net (code "34") (name "Net-(J6-Pad1)") (class "Default")
      (node (ref "J6") (pin "1") (pinfunction "1_1") (pintype "passive"))
      (node (ref "R7") (pin "2") (pinfunction "2_2") (pintype "passive"))
      (node (ref "R8") (pin "1") (pinfunction "1_1") (pintype "passive"))
    )
    (net (code "35") (name "Net-(J6-Pad4)") (class "Default")
      (node (ref "J6") (pin "4") (pinfunction "4_4") (pintype "passive"))
      (node (ref "R16") (pin "2") (pinfunction "2_2") (pintype "passive"))
    )
    (net (code "36") (name "Net-(J7-Pad1)") (class "Default")
      (node (ref "J7") (pin "1") (pinfunction "1_1") (pintype "passive"))
      (node (ref "R8") (pin "2") (pinfunction "2_2") (pintype "passive"))
      (node (ref "R9") (pin "1") (pinfunction "1_1") (pintype "passive"))
    )
    (net (code "37") (name "Net-(J7-Pad4)") (class "Default")
      (node (ref "J7") (pin "4") (pinfunction "4_4") (pintype "passive"))
      (node (ref "R17") (pin "2") (pinfunction "2_2") (pintype "passive"))
    )
    (net (code "38") (name "Net-(J8-Pad4)") (class "Default")
      (node (ref "J8") (pin "4") (pinfunction "4_4") (pintype "passive"))
      (node (ref "R18") (pin "2") (pinfunction "2_2") (pintype "passive"))
    )
    (net (code "39") (name "Net-(J9-1)") (class "Default")
      (node (ref "J9") (pin "P1") (pinfunction "1_P1") (pintype "passive"))
      (node (ref "U$1") (pin "8") (pinfunction "SPK_2_8") (pintype "bidirectional"))
    )
    (net (code "40") (name "Net-(J9-2)") (class "Default")
      (node (ref "J9") (pin "P2") (pinfunction "2_P2") (pintype "passive"))
      (node (ref "U$1") (pin "6") (pinfunction "SPK_1_6") (pintype "bidirectional"))
    )
    (net (code "41") (name "Net-(LED1-PadA)") (class "Default")
      (node (ref "LED1") (pin "A") (pinfunction "A_A") (pintype "passive"))
      (node (ref "R23") (pin "3") (pinfunction "3_3") (pintype "passive"))
    )
    (net (code "42") (name "Net-(LED6-PadA)") (class "Default")
      (node (ref "LED6") (pin "A") (pinfunction "A_A") (pintype "passive"))
      (node (ref "R53") (pin "3") (pinfunction "3_3") (pintype "passive"))
    )
    (net (code "43") (name "Net-(LED8-PadA)") (class "Default")
      (node (ref "LED8") (pin "A") (pinfunction "A_A") (pintype "passive"))
      (node (ref "R54") (pin "3") (pinfunction "3_3") (pintype "passive"))
    )
    (net (code "44") (name "Net-(LED9-PadA)") (class "Default")
      (node (ref "LED9") (pin "A") (pinfunction "A_A") (pintype "passive"))
      (node (ref "R55") (pin "3") (pinfunction "3_3") (pintype "passive"))
    )
    (net (code "45") (name "Net-(LED10-PadA)") (class "Default")
      (node (ref "LED10") (pin "A") (pinfunction "A_A") (pintype "passive"))
      (node (ref "R56") (pin "3") (pinfunction "3_3") (pintype "passive"))
    )
    (net (code "46") (name "Net-(MCP0-GPA4)") (class "Default")
      (node (ref "MCP0") (pin "25") (pinfunction "GPA4_25") (pintype "bidirectional"))
      (node (ref "R11") (pin "1") (pinfunction "1_1") (pintype "passive"))
    )
    (net (code "47") (name "Net-(MCP0-GPA5)") (class "Default")
      (node (ref "MCP0") (pin "26") (pinfunction "GPA5_26") (pintype "bidirectional"))
      (node (ref "R12") (pin "1") (pinfunction "1_1") (pintype "passive"))
    )
    (net (code "48") (name "Net-(MCP0-GPA6)") (class "Default")
      (node (ref "MCP0") (pin "27") (pinfunction "GPA6_27") (pintype "bidirectional"))
      (node (ref "R13") (pin "1") (pinfunction "1_1") (pintype "passive"))
    )
    (net (code "49") (name "Net-(MCP0-GPA7)") (class "Default")
      (node (ref "MCP0") (pin "28") (pinfunction "GPA7_28") (pintype "bidirectional"))
      (node (ref "R14") (pin "1") (pinfunction "1_1") (pintype "passive"))
    )
    (net (code "50") (name "Net-(MCP0-GPB0)") (class "Default")
      (node (ref "MCP0") (pin "1") (pinfunction "GPB0_1") (pintype "bidirectional"))
      (node (ref "R15") (pin "1") (pinfunction "1_1") (pintype "passive"))
    )
    (net (code "51") (name "Net-(MCP0-GPB1)") (class "Default")
      (node (ref "MCP0") (pin "2") (pinfunction "GPB1_2") (pintype "bidirectional"))
      (node (ref "R16") (pin "1") (pinfunction "1_1") (pintype "passive"))
    )
    (net (code "52") (name "Net-(MCP0-GPB2)") (class "Default")
      (node (ref "MCP0") (pin "3") (pinfunction "GPB2_3") (pintype "bidirectional"))
      (node (ref "R17") (pin "1") (pinfunction "1_1") (pintype "passive"))
    )
    (net (code "53") (name "Net-(MCP0-GPB3)") (class "Default")
      (node (ref "MCP0") (pin "4") (pinfunction "GPB3_4") (pintype "bidirectional"))
      (node (ref "R18") (pin "1") (pinfunction "1_1") (pintype "passive"))
    )
    (net (code "54") (name "Net-(MCP0-SCL)") (class "Default")
      (node (ref "B1") (pin "A5") (pinfunction "A5_A5") (pintype "bidirectional"))
      (node (ref "MCP0") (pin "12") (pinfunction "SCL_12") (pintype "input"))
      (node (ref "MCP1") (pin "12") (pinfunction "SCL_12") (pintype "input"))
      (node (ref "R24") (pin "2") (pinfunction "2_2") (pintype "passive"))
    )
    (net (code "55") (name "Net-(MCP0-SDA)") (class "Default")
      (node (ref "B1") (pin "A4") (pinfunction "A4_A4") (pintype "bidirectional"))
      (node (ref "MCP0") (pin "13") (pinfunction "SDA_13") (pintype "bidirectional"))
      (node (ref "MCP1") (pin "13") (pinfunction "SDA_13") (pintype "bidirectional"))
      (node (ref "R25") (pin "2") (pinfunction "2_2") (pintype "passive"))
    )
    (net (code "56") (name "Net-(MCP0-~{RESET})") (class "Default")
      (node (ref "MCP0") (pin "18") (pinfunction "~{RESET}_18") (pintype "input"))
      (node (ref "R20") (pin "2") (pinfunction "2_2") (pintype "passive"))
    )
    (net (code "57") (name "Net-(MCP1-GPA0)") (class "Default")
      (node (ref "MCP1") (pin "21") (pinfunction "GPA0_21") (pintype "bidirectional"))
      (node (ref "R27") (pin "2") (pinfunction "2_2") (pintype "passive"))
    )
    (net (code "58") (name "Net-(MCP1-GPA1)") (class "Default")
      (node (ref "MCP1") (pin "22") (pinfunction "GPA1_22") (pintype "bidirectional"))
      (node (ref "R28") (pin "2") (pinfunction "2_2") (pintype "passive"))
    )
    (net (code "59") (name "Net-(MCP1-GPA2)") (class "Default")
      (node (ref "MCP1") (pin "23") (pinfunction "GPA2_23") (pintype "bidirectional"))
      (node (ref "R29") (pin "2") (pinfunction "2_2") (pintype "passive"))
    )
    (net (code "60") (name "Net-(MCP1-GPA3)") (class "Default")
      (node (ref "MCP1") (pin "24") (pinfunction "GPA3_24") (pintype "bidirectional"))
      (node (ref "R30") (pin "2") (pinfunction "2_2") (pintype "passive"))
    )
    (net (code "61") (name "Net-(MCP1-GPA4)") (class "Default")
      (node (ref "MCP1") (pin "25") (pinfunction "GPA4_25") (pintype "bidirectional"))
      (node (ref "R31") (pin "2") (pinfunction "2_2") (pintype "passive"))
    )
    (net (code "62") (name "Net-(MCP1-GPA5)") (class "Default")
      (node (ref "MCP1") (pin "26") (pinfunction "GPA5_26") (pintype "bidirectional"))
      (node (ref "R32") (pin "2") (pinfunction "2_2") (pintype "passive"))
    )
    (net (code "63") (name "Net-(MCP1-GPA6)") (class "Default")
      (node (ref "MCP1") (pin "27") (pinfunction "GPA6_27") (pintype "bidirectional"))
      (node (ref "R33") (pin "2") (pinfunction "2_2") (pintype "passive"))
    )
    (net (code "64") (name "Net-(MCP1-GPA7)") (class "Default")
      (node (ref "MCP1") (pin "28") (pinfunction "GPA7_28") (pintype "bidirectional"))
      (node (ref "R34") (pin "2") (pinfunction "2_2") (pintype "passive"))
    )
    (net (code "65") (name "Net-(MCP1-GPB0)") (class "Default")
      (node (ref "MCP1") (pin "1") (pinfunction "GPB0_1") (pintype "bidirectional"))
      (node (ref "R35") (pin "2") (pinfunction "2_2") (pintype "passive"))
    )
    (net (code "66") (name "Net-(MCP1-GPB1)") (class "Default")
      (node (ref "MCP1") (pin "2") (pinfunction "GPB1_2") (pintype "bidirectional"))
      (node (ref "R36") (pin "2") (pinfunction "2_2") (pintype "passive"))
    )
    (net (code "67") (name "Net-(MCP1-GPB2)") (class "Default")
      (node (ref "MCP1") (pin "3") (pinfunction "GPB2_3") (pintype "bidirectional"))
      (node (ref "R37") (pin "2") (pinfunction "2_2") (pintype "passive"))
    )
    (net (code "68") (name "Net-(MCP1-GPB3)") (class "Default")
      (node (ref "MCP1") (pin "4") (pinfunction "GPB3_4") (pintype "bidirectional"))
      (node (ref "R38") (pin "2") (pinfunction "2_2") (pintype "passive"))
    )
    (net (code "69") (name "Net-(MCP1-GPB4)") (class "Default")
      (node (ref "MCP1") (pin "5") (pinfunction "GPB4_5") (pintype "bidirectional"))
      (node (ref "R39") (pin "2") (pinfunction "2_2") (pintype "passive"))
    )
    (net (code "70") (name "Net-(MCP1-GPB5)") (class "Default")
      (node (ref "MCP1") (pin "6") (pinfunction "GPB5_6") (pintype "bidirectional"))
      (node (ref "R40") (pin "2") (pinfunction "2_2") (pintype "passive"))
    )
    (net (code "71") (name "Net-(MCP1-GPB6)") (class "Default")
      (node (ref "MCP1") (pin "7") (pinfunction "GPB6_7") (pintype "bidirectional"))
      (node (ref "R41") (pin "2") (pinfunction "2_2") (pintype "passive"))
    )
    (net (code "72") (name "Net-(MCP1-GPB7)") (class "Default")
      (node (ref "MCP1") (pin "8") (pinfunction "GPB7_8") (pintype "bidirectional"))
      (node (ref "R42") (pin "2") (pinfunction "2_2") (pintype "passive"))
    )
    (net (code "73") (name "Net-(MCP1-~{RESET})") (class "Default")
      (node (ref "MCP1") (pin "18") (pinfunction "~{RESET}_18") (pintype "input"))
      (node (ref "R22") (pin "2") (pinfunction "2_2") (pintype "passive"))
    )
    (net (code "74") (name "Net-(NAPPE-LED1-C)") (class "Default")
      (node (ref "NAPPE-LED") (pin "A") (pinfunction "A_A") (pintype "passive"))
      (node (ref "NAPPE-LED1") (pin "K") (pinfunction "C_K") (pintype "passive"))
    )
    (net (code "75") (name "Net-(NAPPE-LED2-C)") (class "Default")
      (node (ref "NAPPE-LED1") (pin "A") (pinfunction "A_A") (pintype "passive"))
      (node (ref "NAPPE-LED2") (pin "K") (pinfunction "C_K") (pintype "passive"))
    )
    (net (code "76") (name "Net-(NAPPE-LED2-PadA)") (class "Default")
      (node (ref "NAPPE-LED2") (pin "A") (pinfunction "A_A") (pintype "passive"))
      (node (ref "R47") (pin "2") (pinfunction "2_2") (pintype "passive"))
    )
    (net (code "77") (name "Net-(NAPPE-LED4-C)") (class "Default")
      (node (ref "NAPPE-LED3") (pin "A") (pinfunction "A_A") (pintype "passive"))
      (node (ref "NAPPE-LED4") (pin "K") (pinfunction "C_K") (pintype "passive"))
    )
    (net (code "78") (name "Net-(NAPPE-LED5-C)") (class "Default")
      (node (ref "NAPPE-LED4") (pin "A") (pinfunction "A_A") (pintype "passive"))
      (node (ref "NAPPE-LED5") (pin "K") (pinfunction "C_K") (pintype "passive"))
    )
    (net (code "79") (name "Net-(NAPPE-LED5-PadA)") (class "Default")
      (node (ref "NAPPE-LED5") (pin "A") (pinfunction "A_A") (pintype "passive"))
      (node (ref "R49") (pin "2") (pinfunction "2_2") (pintype "passive"))
    )
    (net (code "80") (name "Net-(NAPPE-LED7-C)") (class "Default")
      (node (ref "NAPPE-LED6") (pin "A") (pinfunction "A_A") (pintype "passive"))
      (node (ref "NAPPE-LED7") (pin "K") (pinfunction "C_K") (pintype "passive"))
    )
    (net (code "81") (name "Net-(NAPPE-LED8-C)") (class "Default")
      (node (ref "NAPPE-LED7") (pin "A") (pinfunction "A_A") (pintype "passive"))
      (node (ref "NAPPE-LED8") (pin "K") (pinfunction "C_K") (pintype "passive"))
    )
    (net (code "82") (name "Net-(NAPPE-LED8-PadA)") (class "Default")
      (node (ref "NAPPE-LED8") (pin "A") (pinfunction "A_A") (pintype "passive"))
      (node (ref "R50") (pin "2") (pinfunction "2_2") (pintype "passive"))
    )
    (net (code "83") (name "Net-(NAPPE-LED10-C)") (class "Default")
      (node (ref "NAPPE-LED10") (pin "K") (pinfunction "C_K") (pintype "passive"))
      (node (ref "NAPPE-LED9") (pin "A") (pinfunction "A_A") (pintype "passive"))
    )
    (net (code "84") (name "Net-(NAPPE-LED11-C)") (class "Default")
      (node (ref "NAPPE-LED10") (pin "A") (pinfunction "A_A") (pintype "passive"))
      (node (ref "NAPPE-LED11") (pin "K") (pinfunction "C_K") (pintype "passive"))
    )
    (net (code "85") (name "Net-(NAPPE-LED11-PadA)") (class "Default")
      (node (ref "NAPPE-LED11") (pin "A") (pinfunction "A_A") (pintype "passive"))
      (node (ref "R51") (pin "2") (pinfunction "2_2") (pintype "passive"))
    )
    (net (code "86") (name "Net-(NAPPE-LED12-PadA)") (class "Default")
      (node (ref "NAPPE-LED12") (pin "A") (pinfunction "A_A") (pintype "passive"))
      (node (ref "R52") (pin "1") (pinfunction "1_1") (pintype "passive"))
    )
    (net (code "87") (name "Net-(T1-B)") (class "Default")
      (node (ref "R27") (pin "1") (pinfunction "1_1") (pintype "passive"))
      (node (ref "T1") (pin "2") (pinfunction "B_2") (pintype "passive"))
    )
    (net (code "88") (name "Net-(T1-C)") (class "Default")
      (node (ref "J10") (pin "2") (pinfunction "2_2") (pintype "passive"))
      (node (ref "T1") (pin "3") (pinfunction "C_3") (pintype "passive"))
    )
    (net (code "89") (name "Net-(T2-B)") (class "Default")
      (node (ref "R28") (pin "1") (pinfunction "1_1") (pintype "passive"))
      (node (ref "T2") (pin "2") (pinfunction "B_2") (pintype "passive"))
    )
    (net (code "90") (name "Net-(T2-C)") (class "Default")
      (node (ref "J10") (pin "3") (pinfunction "3_3") (pintype "passive"))
      (node (ref "T2") (pin "3") (pinfunction "C_3") (pintype "passive"))
    )
    (net (code "91") (name "Net-(T3-B)") (class "Default")
      (node (ref "R29") (pin "1") (pinfunction "1_1") (pintype "passive"))
      (node (ref "T3") (pin "2") (pinfunction "B_2") (pintype "passive"))
    )
    (net (code "92") (name "Net-(T3-C)") (class "Default")
      (node (ref "J10") (pin "4") (pinfunction "4_4") (pintype "passive"))
      (node (ref "T3") (pin "3") (pinfunction "C_3") (pintype "passive"))
    )
    (net (code "93") (name "Net-(T4-B)") (class "Default")
      (node (ref "R30") (pin "1") (pinfunction "1_1") (pintype "passive"))
      (node (ref "T4") (pin "2") (pinfunction "B_2") (pintype "passive"))
    )
    (net (code "94") (name "Net-(T4-C)") (class "Default")
      (node (ref "J10") (pin "5") (pinfunction "5_5") (pintype "passive"))
      (node (ref "T4") (pin "3") (pinfunction "C_3") (pintype "passive"))
    )
    (net (code "95") (name "Net-(T5-B)") (class "Default")
      (node (ref "R31") (pin "1") (pinfunction "1_1") (pintype "passive"))
      (node (ref "T5") (pin "2") (pinfunction "B_2") (pintype "passive"))
    )
    (net (code "96") (name "Net-(T5-C)") (class "Default")
      (node (ref "J10") (pin "6") (pinfunction "6_6") (pintype "passive"))
      (node (ref "T5") (pin "3") (pinfunction "C_3") (pintype "passive"))
    )
    (net (code "97") (name "Net-(T6-B)") (class "Default")
      (node (ref "R32") (pin "1") (pinfunction "1_1") (pintype "passive"))
      (node (ref "T6") (pin "2") (pinfunction "B_2") (pintype "passive"))
    )
    (net (code "98") (name "Net-(T6-C)") (class "Default")
      (node (ref "J10") (pin "7") (pinfunction "7_7") (pintype "passive"))
      (node (ref "T6") (pin "3") (pinfunction "C_3") (pintype "passive"))
    )
    (net (code "99") (name "Net-(T7-B)") (class "Default")
      (node (ref "R33") (pin "1") (pinfunction "1_1") (pintype "passive"))
      (node (ref "T7") (pin "2") (pinfunction "B_2") (pintype "passive"))
    )
    (net (code "100") (name "Net-(T7-C)") (class "Default")
      (node (ref "J10") (pin "8") (pinfunction "8_8") (pintype "passive"))
      (node (ref "T7") (pin "3") (pinfunction "C_3") (pintype "passive"))
    )
    (net (code "101") (name "Net-(T8-B)") (class "Default")
      (node (ref "R34") (pin "1") (pinfunction "1_1") (pintype "passive"))
      (node (ref "T8") (pin "2") (pinfunction "B_2") (pintype "passive"))
    )
    (net (code "102") (name "Net-(T8-C)") (class "Default")
      (node (ref "J10") (pin "9") (pinfunction "9_9") (pintype "passive"))
      (node (ref "T8") (pin "3") (pinfunction "C_3") (pintype "passive"))
    )
    (net (code "103") (name "Net-(T9-B)") (class "Default")
      (node (ref "R35") (pin "1") (pinfunction "1_1") (pintype "passive"))
      (node (ref "T9") (pin "2") (pinfunction "B_2") (pintype "passive"))
    )
    (net (code "104") (name "Net-(T9-C)") (class "Default")
      (node (ref "J12") (pin "2") (pinfunction "2_2") (pintype "passive"))
      (node (ref "T9") (pin "3") (pinfunction "C_3") (pintype "passive"))
    )
    (net (code "105") (name "Net-(T10-B)") (class "Default")
      (node (ref "R36") (pin "1") (pinfunction "1_1") (pintype "passive"))
      (node (ref "T10") (pin "2") (pinfunction "B_2") (pintype "passive"))
    )
    (net (code "106") (name "Net-(T10-C)") (class "Default")
      (node (ref "J12") (pin "3") (pinfunction "3_3") (pintype "passive"))
      (node (ref "T10") (pin "3") (pinfunction "C_3") (pintype "passive"))
    )
    (net (code "107") (name "Net-(T11-B)") (class "Default")
      (node (ref "R37") (pin "1") (pinfunction "1_1") (pintype "passive"))
      (node (ref "T11") (pin "2") (pinfunction "B_2") (pintype "passive"))
    )
    (net (code "108") (name "Net-(T11-C)") (class "Default")
      (node (ref "J12") (pin "4") (pinfunction "4_4") (pintype "passive"))
      (node (ref "T11") (pin "3") (pinfunction "C_3") (pintype "passive"))
    )
    (net (code "109") (name "Net-(T12-B)") (class "Default")
      (node (ref "R38") (pin "1") (pinfunction "1_1") (pintype "passive"))
      (node (ref "T12") (pin "2") (pinfunction "B_2") (pintype "passive"))
    )
    (net (code "110") (name "Net-(T12-C)") (class "Default")
      (node (ref "J12") (pin "5") (pinfunction "5_5") (pintype "passive"))
      (node (ref "T12") (pin "3") (pinfunction "C_3") (pintype "passive"))
    )
    (net (code "111") (name "Net-(T13-B)") (class "Default")
      (node (ref "R39") (pin "1") (pinfunction "1_1") (pintype "passive"))
      (node (ref "T13") (pin "2") (pinfunction "B_2") (pintype "passive"))
    )
    (net (code "112") (name "Net-(T13-C)") (class "Default")
      (node (ref "J12") (pin "6") (pinfunction "6_6") (pintype "passive"))
      (node (ref "T13") (pin "3") (pinfunction "C_3") (pintype "passive"))
    )
    (net (code "113") (name "Net-(T14-B)") (class "Default")
      (node (ref "R40") (pin "1") (pinfunction "1_1") (pintype "passive"))
      (node (ref "T14") (pin "2") (pinfunction "B_2") (pintype "passive"))
    )
    (net (code "114") (name "Net-(T14-C)") (class "Default")
      (node (ref "J12") (pin "7") (pinfunction "7_7") (pintype "passive"))
      (node (ref "T14") (pin "3") (pinfunction "C_3") (pintype "passive"))
    )
    (net (code "115") (name "Net-(T15-B)") (class "Default")
      (node (ref "R41") (pin "1") (pinfunction "1_1") (pintype "passive"))
      (node (ref "T15") (pin "2") (pinfunction "B_2") (pintype "passive"))
    )
    (net (code "116") (name "Net-(T15-C)") (class "Default")
      (node (ref "J12") (pin "8") (pinfunction "8_8") (pintype "passive"))
      (node (ref "T15") (pin "3") (pinfunction "C_3") (pintype "passive"))
    )
    (net (code "117") (name "Net-(T16-B)") (class "Default")
      (node (ref "R42") (pin "1") (pinfunction "1_1") (pintype "passive"))
      (node (ref "T16") (pin "2") (pinfunction "B_2") (pintype "passive"))
    )
    (net (code "118") (name "Net-(T16-C)") (class "Default")
      (node (ref "J12") (pin "9") (pinfunction "9_9") (pintype "passive"))
      (node (ref "T16") (pin "3") (pinfunction "C_3") (pintype "passive"))
    )
    (net (code "119") (name "Net-(U$1-BUSY)") (class "Default")
      (node (ref "B1") (pin "D12") (pinfunction "D12_D12") (pintype "bidirectional"))
      (node (ref "U$1") (pin "16") (pinfunction "BUSY_16") (pintype "bidirectional"))
    )
    (net (code "120") (name "Net-(U$1-RX)") (class "Default")
      (node (ref "R19") (pin "2") (pinfunction "2_2") (pintype "passive"))
      (node (ref "U$1") (pin "2") (pinfunction "RX_2") (pintype "bidirectional"))
    )
    (net (code "121") (name "Net-(U$1-TX)") (class "Default")
      (node (ref "R10") (pin "2") (pinfunction "2_2") (pintype "passive"))
      (node (ref "U$1") (pin "3") (pinfunction "TX_3") (pintype "bidirectional"))
    )
    (net (code "122") (name "unconnected-(B1-GND-PadGND@0)") (class "Default")
      (node (ref "B1") (pin "GND@0") (pinfunction "GND_GND@0") (pintype "bidirectional"))
    )
    (net (code "123") (name "unconnected-(B1-GND-PadGND@1)") (class "Default")
      (node (ref "B1") (pin "GND@1") (pinfunction "GND_GND@1") (pintype "bidirectional"))
    )
    (net (code "124") (name "unconnected-(B1-Pad3.3V)") (class "Default")
      (node (ref "B1") (pin "3.3V") (pinfunction "3.3V_3.3V") (pintype "bidirectional"))
    )
    (net (code "125") (name "unconnected-(B1-Pad5V)") (class "Default")
      (node (ref "B1") (pin "5V") (pinfunction "5V_5V") (pintype "bidirectional"))
    )
    (net (code "126") (name "unconnected-(B1-PadA0)") (class "Default")
      (node (ref "B1") (pin "A0") (pinfunction "A0_A0") (pintype "bidirectional"))
    )
    (net (code "127") (name "unconnected-(B1-PadA1)") (class "Default")
      (node (ref "B1") (pin "A1") (pinfunction "A1_A1") (pintype "bidirectional"))
    )
    (net (code "128") (name "unconnected-(B1-PadA2)") (class "Default")
      (node (ref "B1") (pin "A2") (pinfunction "A2_A2") (pintype "bidirectional"))
    )
    (net (code "129") (name "unconnected-(B1-PadAREF)") (class "Default")
      (node (ref "B1") (pin "AREF") (pinfunction "AREF_AREF") (pintype "bidirectional"))
    )
    (net (code "130") (name "unconnected-(B1-PadD8)") (class "Default")
      (node (ref "B1") (pin "D8") (pinfunction "D8_D8") (pintype "bidirectional"))
    )
    (net (code "131") (name "unconnected-(B1-PadIOREF)") (class "Default")
      (node (ref "B1") (pin "IOREF") (pinfunction "IOREF_IOREF") (pintype "bidirectional"))
    )
    (net (code "132") (name "unconnected-(B1-PadSCL)") (class "Default")
      (node (ref "B1") (pin "SCL") (pinfunction "SCL_SCL") (pintype "bidirectional"))
    )
    (net (code "133") (name "unconnected-(B1-PadSDA)") (class "Default")
      (node (ref "B1") (pin "SDA") (pinfunction "SDA_SDA") (pintype "bidirectional"))
    )
    (net (code "134") (name "unconnected-(MCP0-GPA0-Pad21)") (class "Default")
      (node (ref "MCP0") (pin "21") (pinfunction "GPA0_21") (pintype "bidirectional"))
    )
    (net (code "135") (name "unconnected-(MCP0-GPA1-Pad22)") (class "Default")
      (node (ref "MCP0") (pin "22") (pinfunction "GPA1_22") (pintype "bidirectional"))
    )
    (net (code "136") (name "unconnected-(MCP0-GPA2-Pad23)") (class "Default")
      (node (ref "MCP0") (pin "23") (pinfunction "GPA2_23") (pintype "bidirectional"))
    )
    (net (code "137") (name "unconnected-(MCP0-GPA3-Pad24)") (class "Default")
      (node (ref "MCP0") (pin "24") (pinfunction "GPA3_24") (pintype "bidirectional"))
    )
    (net (code "138") (name "unconnected-(MCP0-GPB4-Pad5)") (class "Default")
      (node (ref "MCP0") (pin "5") (pinfunction "GPB4_5") (pintype "bidirectional"))
    )
    (net (code "139") (name "unconnected-(MCP0-GPB5-Pad6)") (class "Default")
      (node (ref "MCP0") (pin "6") (pinfunction "GPB5_6") (pintype "bidirectional"))
    )
    (net (code "140") (name "unconnected-(MCP0-GPB6-Pad7)") (class "Default")
      (node (ref "MCP0") (pin "7") (pinfunction "GPB6_7") (pintype "bidirectional"))
    )
    (net (code "141") (name "unconnected-(MCP0-GPB7-Pad8)") (class "Default")
      (node (ref "MCP0") (pin "8") (pinfunction "GPB7_8") (pintype "bidirectional"))
    )
    (net (code "142") (name "unconnected-(MCP0-INTA-Pad20)") (class "Default")
      (node (ref "MCP0") (pin "20") (pinfunction "INTA_20") (pintype "output"))
    )
    (net (code "143") (name "unconnected-(MCP0-INTB-Pad19)") (class "Default")
      (node (ref "MCP0") (pin "19") (pinfunction "INTB_19") (pintype "output"))
    )
    (net (code "144") (name "unconnected-(MCP1-INTA-Pad20)") (class "Default")
      (node (ref "MCP1") (pin "20") (pinfunction "INTA_20") (pintype "output"))
    )
    (net (code "145") (name "unconnected-(MCP1-INTB-Pad19)") (class "Default")
      (node (ref "MCP1") (pin "19") (pinfunction "INTB_19") (pintype "output"))
    )
    (net (code "146") (name "unconnected-(SP1-1-Pad+)") (class "Default")
      (node (ref "SP1") (pin "+") (pinfunction "1_+") (pintype "passive"))
    )
    (net (code "147") (name "unconnected-(SP1-2-Pad-)") (class "Default")
      (node (ref "SP1") (pin "-") (pinfunction "2_-") (pintype "passive"))
    )
    (net (code "148") (name "unconnected-(U$1-ADKEY_1-Pad12)") (class "Default")
      (node (ref "U$1") (pin "12") (pinfunction "ADKEY_1_12") (pintype "bidirectional"))
    )
    (net (code "149") (name "unconnected-(U$1-ADKEY_2-Pad13)") (class "Default")
      (node (ref "U$1") (pin "13") (pinfunction "ADKEY_2_13") (pintype "bidirectional"))
    )
    (net (code "150") (name "unconnected-(U$1-DAC_I-Pad5)") (class "Default")
      (node (ref "U$1") (pin "5") (pinfunction "DAC_I_5") (pintype "bidirectional"))
    )
    (net (code "151") (name "unconnected-(U$1-DAC_R-Pad4)") (class "Default")
      (node (ref "U$1") (pin "4") (pinfunction "DAC_R_4") (pintype "bidirectional"))
    )
    (net (code "152") (name "unconnected-(U$1-IO_1-Pad9)") (class "Default")
      (node (ref "U$1") (pin "9") (pinfunction "IO_1_9") (pintype "bidirectional"))
    )
    (net (code "153") (name "unconnected-(U$1-IO_2-Pad11)") (class "Default")
      (node (ref "U$1") (pin "11") (pinfunction "IO_2_11") (pintype "bidirectional"))
    )
    (net (code "154") (name "unconnected-(U$1-USB+-Pad14)") (class "Default")
      (node (ref "U$1") (pin "14") (pinfunction "USB+_14") (pintype "bidirectional"))
    )
    (net (code "155") (name "unconnected-(U$1-USB--Pad15)") (class "Default")
      (node (ref "U$1") (pin "15") (pinfunction "USB-_15") (pintype "bidirectional"))
    )
  )
)
